# parking.net
KiCad netlist of a schematic drawn in EAGLE
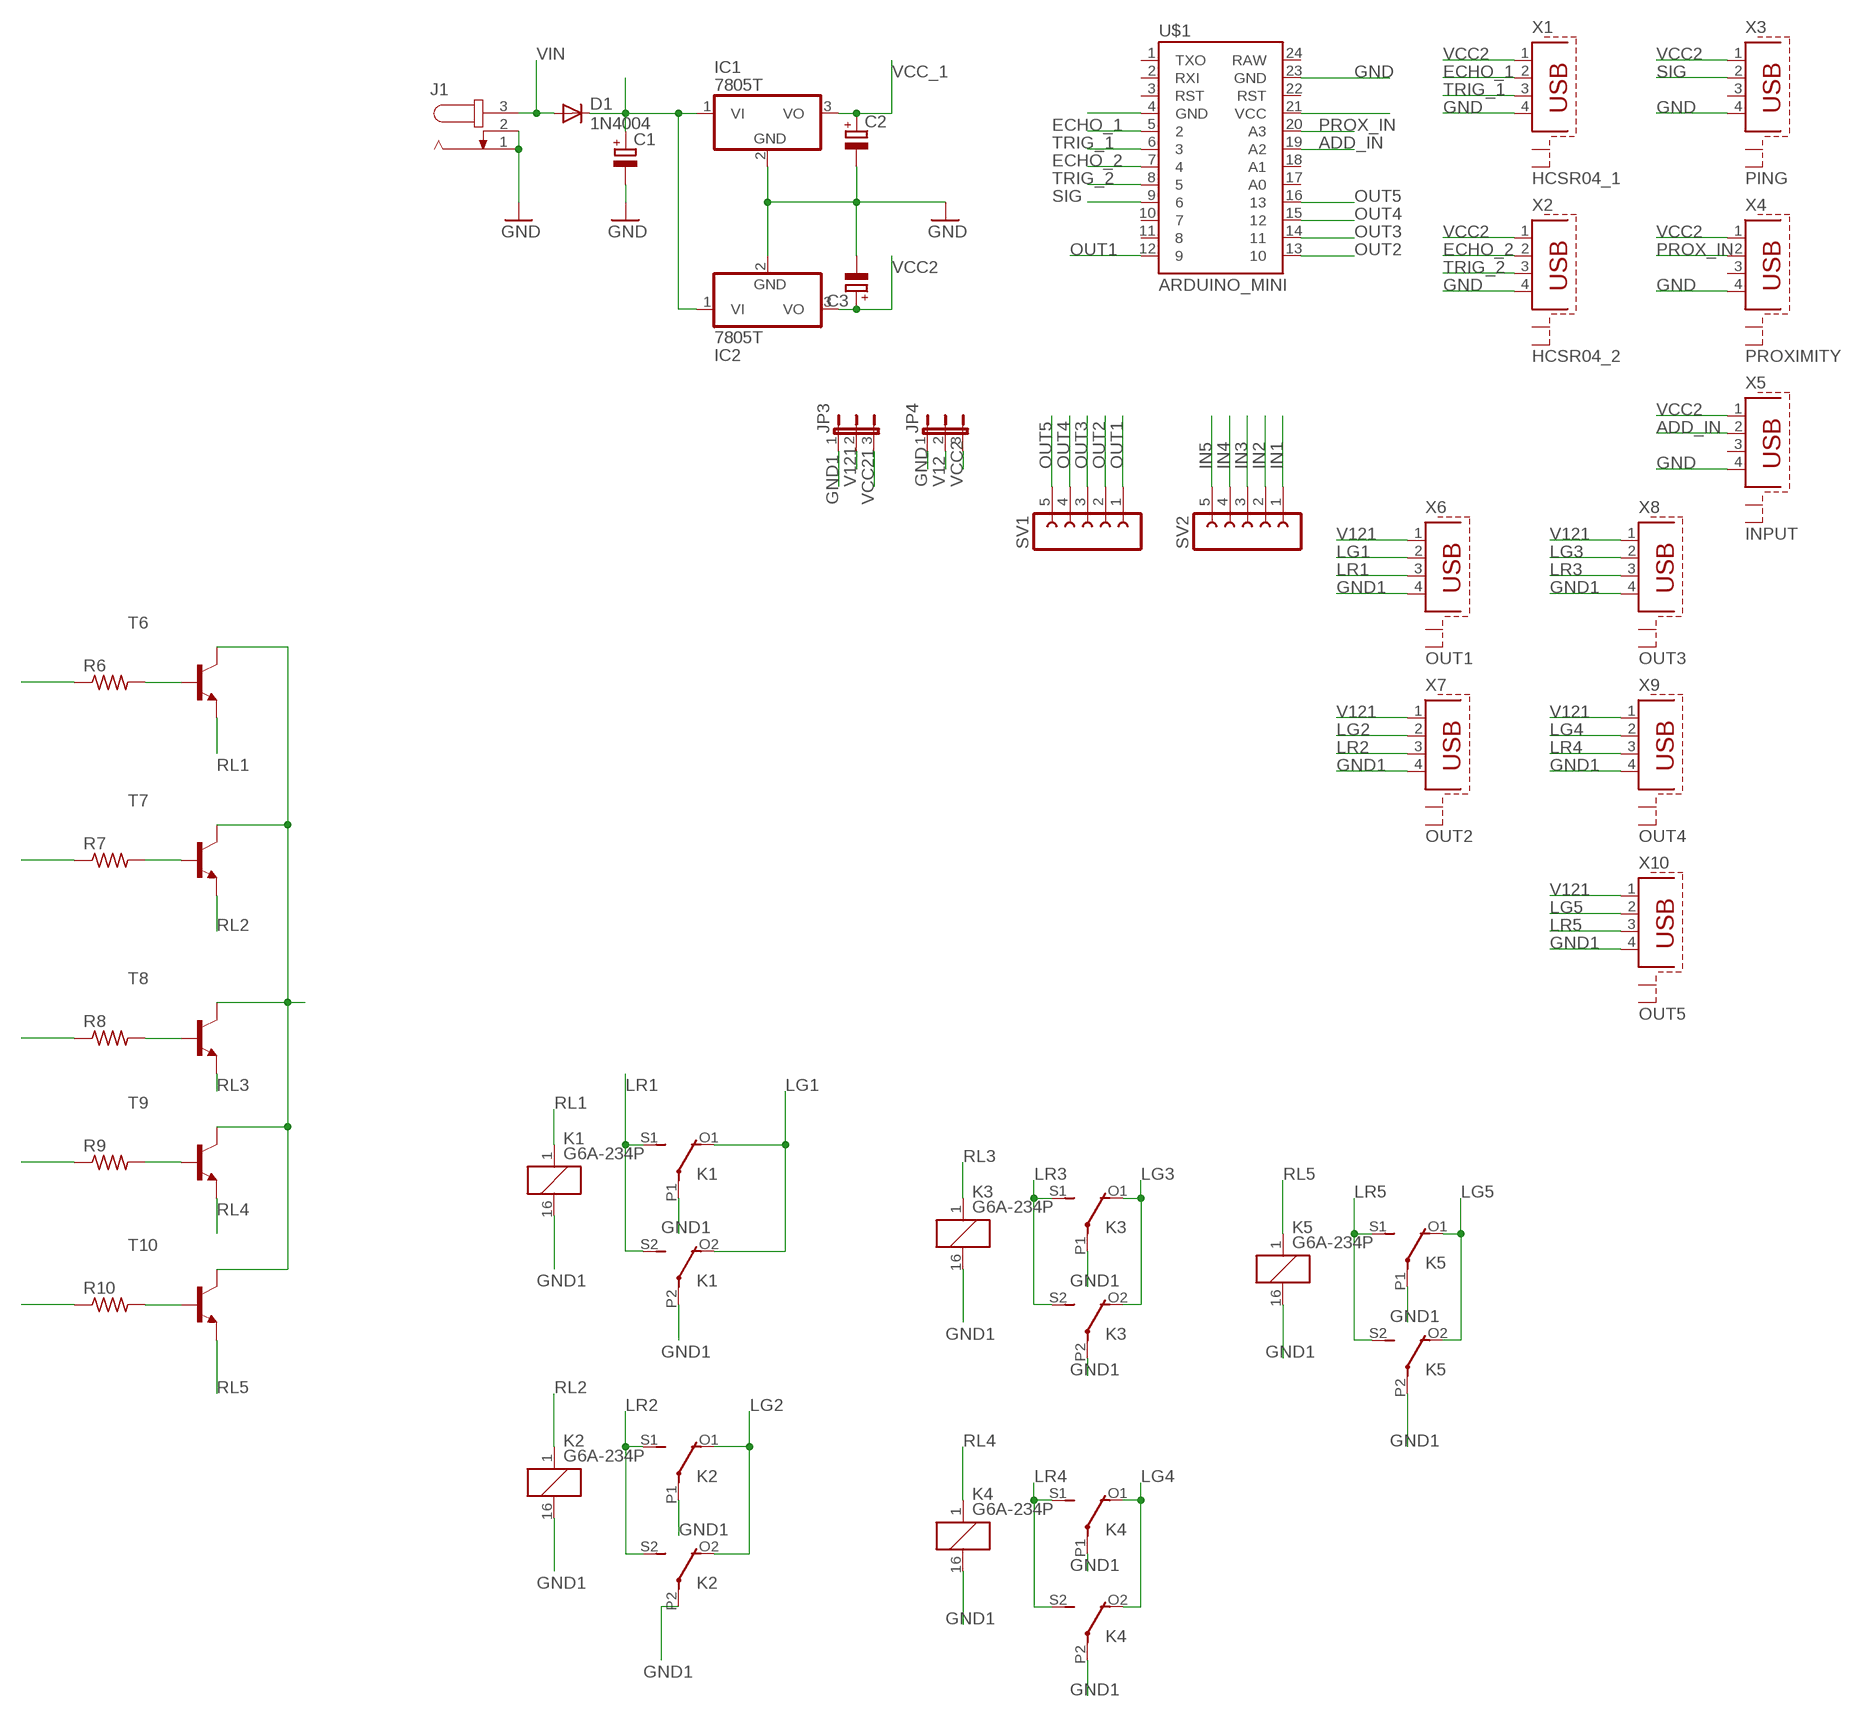
[diagram p0: schematic, sheet 1]

(export (version "E")
  (design (tool "Eeschema 10.0.6"))
  (components
    (comp (ref "C1")
      (value "CPOL-EUE5-10.5")
      (footprint "eagle-import:E5-10,5")
      (libsource (lib "eagle-import") (part "CPOL-EUE5-10.5"))
    )
    (comp (ref "C2")
      (value "CPOL-EUE2.5-5")
      (footprint "eagle-import:E2,5-5")
      (libsource (lib "eagle-import") (part "CPOL-EUE2.5-5"))
    )
    (comp (ref "C3")
      (value "CPOL-EUE2.5-5")
      (footprint "eagle-import:E2,5-5")
      (libsource (lib "eagle-import") (part "CPOL-EUE2.5-5"))
    )
    (comp (ref "D1")
      (value "1N4004")
      (footprint "eagle-import:DO41-10")
      (libsource (lib "eagle-import") (part "1N4004"))
    )
    (comp (ref "IC1")
      (value "7805T")
      (footprint "eagle-import:TO220H")
      (libsource (lib "eagle-import") (part "78T05"))
    )
    (comp (ref "IC2")
      (value "7805T")
      (footprint "eagle-import:TO220H")
      (libsource (lib "eagle-import") (part "78T05"))
    )
    (comp (ref "J1")
      (value "JACK-PLUG1")
      (footprint "eagle-import:SPC4078")
      (libsource (lib "eagle-import") (part "JACK-PLUG1"))
    )
    (comp (ref "JP3")
      (value "JP2E")
      (footprint "eagle-import:JP2")
      (libsource (lib "eagle-import") (part "JP2E"))
    )
    (comp (ref "JP4")
      (value "JP2E")
      (footprint "eagle-import:JP2")
      (libsource (lib "eagle-import") (part "JP2E"))
    )
    (comp (ref "K1")
      (value "G6A-234P")
      (footprint "eagle-import:G6A-234P")
      (libsource (lib "eagle-import") (part "G6A-234P"))
    )
    (comp (ref "K2")
      (value "G6A-234P")
      (footprint "eagle-import:G6A-234P")
      (libsource (lib "eagle-import") (part "G6A-234P"))
    )
    (comp (ref "K3")
      (value "G6A-234P")
      (footprint "eagle-import:G6A-234P")
      (libsource (lib "eagle-import") (part "G6A-234P"))
    )
    (comp (ref "K4")
      (value "G6A-234P")
      (footprint "eagle-import:G6A-234P")
      (libsource (lib "eagle-import") (part "G6A-234P"))
    )
    (comp (ref "K5")
      (value "G6A-234P")
      (footprint "eagle-import:G6A-234P")
      (libsource (lib "eagle-import") (part "G6A-234P"))
    )
    (comp (ref "R6")
      (value "R-US_0207/7")
      (footprint "eagle-import:0207_7")
      (libsource (lib "eagle-import") (part "R-US_0207/7"))
    )
    (comp (ref "R7")
      (value "R-US_0207/7")
      (footprint "eagle-import:0207_7")
      (libsource (lib "eagle-import") (part "R-US_0207/7"))
    )
    (comp (ref "R8")
      (value "R-US_0207/7")
      (footprint "eagle-import:0207_7")
      (libsource (lib "eagle-import") (part "R-US_0207/7"))
    )
    (comp (ref "R9")
      (value "R-US_0207/7")
      (footprint "eagle-import:0207_7")
      (libsource (lib "eagle-import") (part "R-US_0207/7"))
    )
    (comp (ref "R10")
      (value "R-US_0207/7")
      (footprint "eagle-import:0207_7")
      (libsource (lib "eagle-import") (part "R-US_0207/7"))
    )
    (comp (ref "SV1")
      (value "FE05-1")
      (footprint "eagle-import:FE05-1")
      (libsource (lib "eagle-import") (part "FE05-1"))
    )
    (comp (ref "SV2")
      (value "FE05-1")
      (footprint "eagle-import:FE05-1")
      (libsource (lib "eagle-import") (part "FE05-1"))
    )
    (comp (ref "T6")
      (value "BC317-NPN-TO92-EBC")
      (footprint "eagle-import:TO92-EBC")
      (libsource (lib "eagle-import") (part "-NPN-TO92-EBCBC317"))
    )
    (comp (ref "T7")
      (value "BC317-NPN-TO92-EBC")
      (footprint "eagle-import:TO92-EBC")
      (libsource (lib "eagle-import") (part "-NPN-TO92-EBCBC317"))
    )
    (comp (ref "T8")
      (value "BC317-NPN-TO92-EBC")
      (footprint "eagle-import:TO92-EBC")
      (libsource (lib "eagle-import") (part "-NPN-TO92-EBCBC317"))
    )
    (comp (ref "T9")
      (value "BC317-NPN-TO92-EBC")
      (footprint "eagle-import:TO92-EBC")
      (libsource (lib "eagle-import") (part "-NPN-TO92-EBCBC317"))
    )
    (comp (ref "T10")
      (value "BC317-NPN-TO92-EBC")
      (footprint "eagle-import:TO92-EBC")
      (libsource (lib "eagle-import") (part "-NPN-TO92-EBCBC317"))
    )
    (comp (ref "U$1")
      (value "ARDUINO_MINI")
      (footprint "eagle-import:ARDUINO_MINI")
      (libsource (lib "eagle-import") (part "ARDUINO_MINI"))
    )
    (comp (ref "X1")
      (value "HCSR04_1")
      (footprint "eagle-import:PN87520-S")
      (libsource (lib "eagle-import") (part "PN87520-S"))
    )
    (comp (ref "X2")
      (value "HCSR04_2")
      (footprint "eagle-import:PN87520-S")
      (libsource (lib "eagle-import") (part "PN87520-S"))
    )
    (comp (ref "X3")
      (value "PING")
      (footprint "eagle-import:PN87520-S")
      (libsource (lib "eagle-import") (part "PN87520-S"))
    )
    (comp (ref "X4")
      (value "PROXIMITY")
      (footprint "eagle-import:PN87520-S")
      (libsource (lib "eagle-import") (part "PN87520-S"))
    )
    (comp (ref "X5")
      (value "INPUT")
      (footprint "eagle-import:PN87520-S")
      (libsource (lib "eagle-import") (part "PN87520-S"))
    )
    (comp (ref "X6")
      (value "OUT1")
      (footprint "eagle-import:PN87520-S")
      (libsource (lib "eagle-import") (part "PN87520-S"))
    )
    (comp (ref "X7")
      (value "OUT2")
      (footprint "eagle-import:PN87520-S")
      (libsource (lib "eagle-import") (part "PN87520-S"))
    )
    (comp (ref "X8")
      (value "OUT3")
      (footprint "eagle-import:PN87520-S")
      (libsource (lib "eagle-import") (part "PN87520-S"))
    )
    (comp (ref "X9")
      (value "OUT4")
      (footprint "eagle-import:PN87520-S")
      (libsource (lib "eagle-import") (part "PN87520-S"))
    )
    (comp (ref "X10")
      (value "OUT5")
      (footprint "eagle-import:PN87520-S")
      (libsource (lib "eagle-import") (part "PN87520-S"))
    )
  )
  (nets
    (net (code "1") (name "/ADD_IN") (class "Default")
      (node (ref "U$1") (pin "19") (pinfunction "A2_19") (pintype "bidirectional"))
      (node (ref "X5") (pin "2") (pinfunction "2_2") (pintype "passive"))
    )
    (net (code "2") (name "/ECHO_1") (class "Default")
      (node (ref "U$1") (pin "5") (pinfunction "2_5") (pintype "bidirectional"))
      (node (ref "X1") (pin "2") (pinfunction "2_2") (pintype "passive"))
    )
    (net (code "3") (name "/ECHO_2") (class "Default")
      (node (ref "U$1") (pin "7") (pinfunction "4_7") (pintype "bidirectional"))
      (node (ref "X2") (pin "2") (pinfunction "2_2") (pintype "passive"))
    )
    (net (code "4") (name "/GND1") (class "Default")
      (node (ref "JP3") (pin "1") (pinfunction "1_1") (pintype "passive"))
      (node (ref "K1") (pin "16") (pinfunction "2_16") (pintype "passive"))
      (node (ref "K1") (pin "P1") (pinfunction "P_P1") (pintype "passive"))
      (node (ref "K1") (pin "P2") (pinfunction "P_P2") (pintype "passive"))
      (node (ref "K2") (pin "16") (pinfunction "2_16") (pintype "passive"))
      (node (ref "K2") (pin "P1") (pinfunction "P_P1") (pintype "passive"))
      (node (ref "K2") (pin "P2") (pinfunction "P_P2") (pintype "passive"))
      (node (ref "K3") (pin "16") (pinfunction "2_16") (pintype "passive"))
      (node (ref "K3") (pin "P1") (pinfunction "P_P1") (pintype "passive"))
      (node (ref "K3") (pin "P2") (pinfunction "P_P2") (pintype "passive"))
      (node (ref "K4") (pin "16") (pinfunction "2_16") (pintype "passive"))
      (node (ref "K4") (pin "P1") (pinfunction "P_P1") (pintype "passive"))
      (node (ref "K4") (pin "P2") (pinfunction "P_P2") (pintype "passive"))
      (node (ref "K5") (pin "16") (pinfunction "2_16") (pintype "passive"))
      (node (ref "K5") (pin "P1") (pinfunction "P_P1") (pintype "passive"))
      (node (ref "K5") (pin "P2") (pinfunction "P_P2") (pintype "passive"))
      (node (ref "X10") (pin "4") (pinfunction "4_4") (pintype "passive"))
      (node (ref "X6") (pin "4") (pinfunction "4_4") (pintype "passive"))
      (node (ref "X7") (pin "4") (pinfunction "4_4") (pintype "passive"))
      (node (ref "X8") (pin "4") (pinfunction "4_4") (pintype "passive"))
      (node (ref "X9") (pin "4") (pinfunction "4_4") (pintype "passive"))
    )
    (net (code "5") (name "/IN1") (class "Default")
      (node (ref "R6") (pin "1") (pinfunction "1_1") (pintype "passive"))
      (node (ref "SV2") (pin "1") (pinfunction "1_1") (pintype "passive"))
    )
    (net (code "6") (name "/IN2") (class "Default")
      (node (ref "R7") (pin "1") (pinfunction "1_1") (pintype "passive"))
      (node (ref "SV2") (pin "2") (pinfunction "2_2") (pintype "passive"))
    )
    (net (code "7") (name "/IN3") (class "Default")
      (node (ref "R8") (pin "1") (pinfunction "1_1") (pintype "passive"))
      (node (ref "SV2") (pin "3") (pinfunction "3_3") (pintype "passive"))
    )
    (net (code "8") (name "/IN4") (class "Default")
      (node (ref "R9") (pin "1") (pinfunction "1_1") (pintype "passive"))
      (node (ref "SV2") (pin "4") (pinfunction "4_4") (pintype "passive"))
    )
    (net (code "9") (name "/IN5") (class "Default")
      (node (ref "R10") (pin "1") (pinfunction "1_1") (pintype "passive"))
      (node (ref "SV2") (pin "5") (pinfunction "5_5") (pintype "passive"))
    )
    (net (code "10") (name "/LG1") (class "Default")
      (node (ref "K1") (pin "O1") (pinfunction "O_O1") (pintype "passive"))
      (node (ref "K1") (pin "O2") (pinfunction "O_O2") (pintype "passive"))
      (node (ref "X6") (pin "2") (pinfunction "2_2") (pintype "passive"))
    )
    (net (code "11") (name "/LG2") (class "Default")
      (node (ref "K2") (pin "O1") (pinfunction "O_O1") (pintype "passive"))
      (node (ref "K2") (pin "O2") (pinfunction "O_O2") (pintype "passive"))
      (node (ref "X7") (pin "2") (pinfunction "2_2") (pintype "passive"))
    )
    (net (code "12") (name "/LG3") (class "Default")
      (node (ref "K3") (pin "O1") (pinfunction "O_O1") (pintype "passive"))
      (node (ref "K3") (pin "O2") (pinfunction "O_O2") (pintype "passive"))
      (node (ref "X8") (pin "2") (pinfunction "2_2") (pintype "passive"))
    )
    (net (code "13") (name "/LG4") (class "Default")
      (node (ref "K4") (pin "O1") (pinfunction "O_O1") (pintype "passive"))
      (node (ref "K4") (pin "O2") (pinfunction "O_O2") (pintype "passive"))
      (node (ref "X9") (pin "2") (pinfunction "2_2") (pintype "passive"))
    )
    (net (code "14") (name "/LG5") (class "Default")
      (node (ref "K5") (pin "O1") (pinfunction "O_O1") (pintype "passive"))
      (node (ref "K5") (pin "O2") (pinfunction "O_O2") (pintype "passive"))
      (node (ref "X10") (pin "2") (pinfunction "2_2") (pintype "passive"))
    )
    (net (code "15") (name "/LR1") (class "Default")
      (node (ref "K1") (pin "S1") (pinfunction "S_S1") (pintype "passive"))
      (node (ref "K1") (pin "S2") (pinfunction "S_S2") (pintype "passive"))
      (node (ref "X6") (pin "3") (pinfunction "3_3") (pintype "passive"))
    )
    (net (code "16") (name "/LR2") (class "Default")
      (node (ref "K2") (pin "S1") (pinfunction "S_S1") (pintype "passive"))
      (node (ref "K2") (pin "S2") (pinfunction "S_S2") (pintype "passive"))
      (node (ref "X7") (pin "3") (pinfunction "3_3") (pintype "passive"))
    )
    (net (code "17") (name "/LR3") (class "Default")
      (node (ref "K3") (pin "S1") (pinfunction "S_S1") (pintype "passive"))
      (node (ref "K3") (pin "S2") (pinfunction "S_S2") (pintype "passive"))
      (node (ref "X8") (pin "3") (pinfunction "3_3") (pintype "passive"))
    )
    (net (code "18") (name "/LR4") (class "Default")
      (node (ref "K4") (pin "S1") (pinfunction "S_S1") (pintype "passive"))
      (node (ref "K4") (pin "S2") (pinfunction "S_S2") (pintype "passive"))
      (node (ref "X9") (pin "3") (pinfunction "3_3") (pintype "passive"))
    )
    (net (code "19") (name "/LR5") (class "Default")
      (node (ref "K5") (pin "S1") (pinfunction "S_S1") (pintype "passive"))
      (node (ref "K5") (pin "S2") (pinfunction "S_S2") (pintype "passive"))
      (node (ref "X10") (pin "3") (pinfunction "3_3") (pintype "passive"))
    )
    (net (code "20") (name "/OUT1") (class "Default")
      (node (ref "SV1") (pin "1") (pinfunction "1_1") (pintype "passive"))
      (node (ref "U$1") (pin "12") (pinfunction "9_12") (pintype "bidirectional"))
    )
    (net (code "21") (name "/OUT2") (class "Default")
      (node (ref "SV1") (pin "2") (pinfunction "2_2") (pintype "passive"))
      (node (ref "U$1") (pin "13") (pinfunction "10_13") (pintype "bidirectional"))
    )
    (net (code "22") (name "/OUT3") (class "Default")
      (node (ref "SV1") (pin "3") (pinfunction "3_3") (pintype "passive"))
      (node (ref "U$1") (pin "14") (pinfunction "11_14") (pintype "bidirectional"))
    )
    (net (code "23") (name "/OUT4") (class "Default")
      (node (ref "SV1") (pin "4") (pinfunction "4_4") (pintype "passive"))
      (node (ref "U$1") (pin "15") (pinfunction "12_15") (pintype "bidirectional"))
    )
    (net (code "24") (name "/OUT5") (class "Default")
      (node (ref "SV1") (pin "5") (pinfunction "5_5") (pintype "passive"))
      (node (ref "U$1") (pin "16") (pinfunction "13_16") (pintype "bidirectional"))
    )
    (net (code "25") (name "/PROX_IN") (class "Default")
      (node (ref "U$1") (pin "20") (pinfunction "A3_20") (pintype "bidirectional"))
      (node (ref "X4") (pin "2") (pinfunction "2_2") (pintype "passive"))
    )
    (net (code "26") (name "/RL1") (class "Default")
      (node (ref "K1") (pin "1") (pinfunction "1_1") (pintype "passive"))
      (node (ref "T6") (pin "E") (pinfunction "E_E") (pintype "passive"))
    )
    (net (code "27") (name "/RL2") (class "Default")
      (node (ref "K2") (pin "1") (pinfunction "1_1") (pintype "passive"))
      (node (ref "T7") (pin "E") (pinfunction "E_E") (pintype "passive"))
    )
    (net (code "28") (name "/RL3") (class "Default")
      (node (ref "K3") (pin "1") (pinfunction "1_1") (pintype "passive"))
      (node (ref "T8") (pin "E") (pinfunction "E_E") (pintype "passive"))
    )
    (net (code "29") (name "/RL4") (class "Default")
      (node (ref "K4") (pin "1") (pinfunction "1_1") (pintype "passive"))
      (node (ref "T9") (pin "E") (pinfunction "E_E") (pintype "passive"))
    )
    (net (code "30") (name "/RL5") (class "Default")
      (node (ref "K5") (pin "1") (pinfunction "1_1") (pintype "passive"))
      (node (ref "T10") (pin "E") (pinfunction "E_E") (pintype "passive"))
    )
    (net (code "31") (name "/SIG") (class "Default")
      (node (ref "U$1") (pin "9") (pinfunction "6_9") (pintype "bidirectional"))
      (node (ref "X3") (pin "2") (pinfunction "2_2") (pintype "passive"))
    )
    (net (code "32") (name "/TRIG_1") (class "Default")
      (node (ref "U$1") (pin "6") (pinfunction "3_6") (pintype "bidirectional"))
      (node (ref "X1") (pin "3") (pinfunction "3_3") (pintype "passive"))
    )
    (net (code "33") (name "/TRIG_2") (class "Default")
      (node (ref "U$1") (pin "8") (pinfunction "5_8") (pintype "bidirectional"))
      (node (ref "X2") (pin "3") (pinfunction "3_3") (pintype "passive"))
    )
    (net (code "34") (name "/V12") (class "Default")
      (node (ref "C1") (pin "+") (pinfunction "+_+") (pintype "passive"))
      (node (ref "D1") (pin "C") (pinfunction "C_C") (pintype "passive"))
      (node (ref "IC1") (pin "1") (pinfunction "VI_1") (pintype "input"))
      (node (ref "IC2") (pin "1") (pinfunction "VI_1") (pintype "input"))
      (node (ref "JP4") (pin "2") (pinfunction "2_2") (pintype "passive"))
    )
    (net (code "35") (name "/V121") (class "Default")
      (node (ref "JP3") (pin "2") (pinfunction "2_2") (pintype "passive"))
      (node (ref "X10") (pin "1") (pinfunction "1_1") (pintype "passive"))
      (node (ref "X6") (pin "1") (pinfunction "1_1") (pintype "passive"))
      (node (ref "X7") (pin "1") (pinfunction "1_1") (pintype "passive"))
      (node (ref "X8") (pin "1") (pinfunction "1_1") (pintype "passive"))
      (node (ref "X9") (pin "1") (pinfunction "1_1") (pintype "passive"))
    )
    (net (code "36") (name "/VCC2") (class "Default")
      (node (ref "C3") (pin "+") (pinfunction "+_+") (pintype "passive"))
      (node (ref "IC2") (pin "3") (pinfunction "VO_3") (pintype "passive"))
      (node (ref "JP4") (pin "3") (pinfunction "3_3") (pintype "passive"))
      (node (ref "X1") (pin "1") (pinfunction "1_1") (pintype "passive"))
      (node (ref "X2") (pin "1") (pinfunction "1_1") (pintype "passive"))
      (node (ref "X3") (pin "1") (pinfunction "1_1") (pintype "passive"))
      (node (ref "X4") (pin "1") (pinfunction "1_1") (pintype "passive"))
      (node (ref "X5") (pin "1") (pinfunction "1_1") (pintype "passive"))
    )
    (net (code "37") (name "/VCC21") (class "Default")
      (node (ref "JP3") (pin "3") (pinfunction "3_3") (pintype "passive"))
      (node (ref "T10") (pin "C") (pinfunction "C_C") (pintype "passive"))
      (node (ref "T6") (pin "C") (pinfunction "C_C") (pintype "passive"))
      (node (ref "T7") (pin "C") (pinfunction "C_C") (pintype "passive"))
      (node (ref "T8") (pin "C") (pinfunction "C_C") (pintype "passive"))
      (node (ref "T9") (pin "C") (pinfunction "C_C") (pintype "passive"))
    )
    (net (code "38") (name "/VCC_1") (class "Default")
      (node (ref "C2") (pin "+") (pinfunction "+_+") (pintype "passive"))
      (node (ref "IC1") (pin "3") (pinfunction "VO_3") (pintype "passive"))
      (node (ref "U$1") (pin "21") (pinfunction "VCC_21") (pintype "bidirectional"))
    )
    (net (code "39") (name "/VIN") (class "Default")
      (node (ref "D1") (pin "A") (pinfunction "A_A") (pintype "passive"))
      (node (ref "J1") (pin "3") (pinfunction "3_3") (pintype "passive"))
    )
    (net (code "40") (name "GND") (class "Default")
      (node (ref "C1") (pin "-") (pinfunction "-_-") (pintype "passive"))
      (node (ref "C2") (pin "-") (pinfunction "-_-") (pintype "passive"))
      (node (ref "C3") (pin "-") (pinfunction "-_-") (pintype "passive"))
      (node (ref "IC1") (pin "2") (pinfunction "GND_2") (pintype "passive"))
      (node (ref "IC2") (pin "2") (pinfunction "GND_2") (pintype "passive"))
      (node (ref "J1") (pin "1") (pinfunction "1_1") (pintype "passive"))
      (node (ref "J1") (pin "2") (pinfunction "2_2") (pintype "passive"))
      (node (ref "JP4") (pin "1") (pinfunction "1_1") (pintype "passive"))
      (node (ref "U$1") (pin "23") (pinfunction "GND_23") (pintype "bidirectional"))
      (node (ref "U$1") (pin "4") (pinfunction "GND_4") (pintype "bidirectional"))
      (node (ref "X1") (pin "4") (pinfunction "4_4") (pintype "passive"))
      (node (ref "X2") (pin "4") (pinfunction "4_4") (pintype "passive"))
      (node (ref "X3") (pin "4") (pinfunction "4_4") (pintype "passive"))
      (node (ref "X4") (pin "4") (pinfunction "4_4") (pintype "passive"))
      (node (ref "X5") (pin "4") (pinfunction "4_4") (pintype "passive"))
    )
    (net (code "41") (name "Net-(R6-Pad2)") (class "Default")
      (node (ref "R6") (pin "2") (pinfunction "2_2") (pintype "passive"))
      (node (ref "T6") (pin "B") (pinfunction "B_B") (pintype "passive"))
    )
    (net (code "42") (name "Net-(R7-Pad2)") (class "Default")
      (node (ref "R7") (pin "2") (pinfunction "2_2") (pintype "passive"))
      (node (ref "T7") (pin "B") (pinfunction "B_B") (pintype "passive"))
    )
    (net (code "43") (name "Net-(R8-Pad2)") (class "Default")
      (node (ref "R8") (pin "2") (pinfunction "2_2") (pintype "passive"))
      (node (ref "T8") (pin "B") (pinfunction "B_B") (pintype "passive"))
    )
    (net (code "44") (name "Net-(R9-Pad2)") (class "Default")
      (node (ref "R9") (pin "2") (pinfunction "2_2") (pintype "passive"))
      (node (ref "T9") (pin "B") (pinfunction "B_B") (pintype "passive"))
    )
    (net (code "45") (name "Net-(R10-Pad2)") (class "Default")
      (node (ref "R10") (pin "2") (pinfunction "2_2") (pintype "passive"))
      (node (ref "T10") (pin "B") (pinfunction "B_B") (pintype "passive"))
    )
    (net (code "46") (name "unconnected-(U$1-7-Pad10)") (class "Default")
      (node (ref "U$1") (pin "10") (pinfunction "7_10") (pintype "bidirectional"))
    )
    (net (code "47") (name "unconnected-(U$1-8-Pad11)") (class "Default")
      (node (ref "U$1") (pin "11") (pinfunction "8_11") (pintype "bidirectional"))
    )
    (net (code "48") (name "unconnected-(U$1-A0-Pad17)") (class "Default")
      (node (ref "U$1") (pin "17") (pinfunction "A0_17") (pintype "bidirectional"))
    )
    (net (code "49") (name "unconnected-(U$1-A1-Pad18)") (class "Default")
      (node (ref "U$1") (pin "18") (pinfunction "A1_18") (pintype "bidirectional"))
    )
    (net (code "50") (name "unconnected-(U$1-RAW-Pad24)") (class "Default")
      (node (ref "U$1") (pin "24") (pinfunction "RAW_24") (pintype "bidirectional"))
    )
    (net (code "51") (name "unconnected-(U$1-RST-Pad3)") (class "Default")
      (node (ref "U$1") (pin "3") (pinfunction "RST_3") (pintype "bidirectional"))
    )
    (net (code "52") (name "unconnected-(U$1-RST-Pad22)") (class "Default")
      (node (ref "U$1") (pin "22") (pinfunction "RST_22") (pintype "bidirectional"))
    )
    (net (code "53") (name "unconnected-(U$1-RXI-Pad2)") (class "Default")
      (node (ref "U$1") (pin "2") (pinfunction "RXI_2") (pintype "bidirectional"))
    )
    (net (code "54") (name "unconnected-(U$1-TXO-Pad1)") (class "Default")
      (node (ref "U$1") (pin "1") (pinfunction "TXO_1") (pintype "bidirectional"))
    )
    (net (code "55") (name "unconnected-(X1-PadS1)") (class "Default")
      (node (ref "X1") (pin "S1") (pinfunction "S1_S1") (pintype "passive"))
    )
    (net (code "56") (name "unconnected-(X1-PadS2)") (class "Default")
      (node (ref "X1") (pin "S2") (pinfunction "S2_S2") (pintype "passive"))
    )
    (net (code "57") (name "unconnected-(X2-PadS1)") (class "Default")
      (node (ref "X2") (pin "S1") (pinfunction "S1_S1") (pintype "passive"))
    )
    (net (code "58") (name "unconnected-(X2-PadS2)") (class "Default")
      (node (ref "X2") (pin "S2") (pinfunction "S2_S2") (pintype "passive"))
    )
    (net (code "59") (name "unconnected-(X3-Pad3)") (class "Default")
      (node (ref "X3") (pin "3") (pinfunction "3_3") (pintype "passive"))
    )
    (net (code "60") (name "unconnected-(X3-PadS1)") (class "Default")
      (node (ref "X3") (pin "S1") (pinfunction "S1_S1") (pintype "passive"))
    )
    (net (code "61") (name "unconnected-(X3-PadS2)") (class "Default")
      (node (ref "X3") (pin "S2") (pinfunction "S2_S2") (pintype "passive"))
    )
    (net (code "62") (name "unconnected-(X4-Pad3)") (class "Default")
      (node (ref "X4") (pin "3") (pinfunction "3_3") (pintype "passive"))
    )
    (net (code "63") (name "unconnected-(X4-PadS1)") (class "Default")
      (node (ref "X4") (pin "S1") (pinfunction "S1_S1") (pintype "passive"))
    )
    (net (code "64") (name "unconnected-(X4-PadS2)") (class "Default")
      (node (ref "X4") (pin "S2") (pinfunction "S2_S2") (pintype "passive"))
    )
    (net (code "65") (name "unconnected-(X5-Pad3)") (class "Default")
      (node (ref "X5") (pin "3") (pinfunction "3_3") (pintype "passive"))
    )
    (net (code "66") (name "unconnected-(X5-PadS1)") (class "Default")
      (node (ref "X5") (pin "S1") (pinfunction "S1_S1") (pintype "passive"))
    )
    (net (code "67") (name "unconnected-(X5-PadS2)") (class "Default")
      (node (ref "X5") (pin "S2") (pinfunction "S2_S2") (pintype "passive"))
    )
    (net (code "68") (name "unconnected-(X6-PadS1)") (class "Default")
      (node (ref "X6") (pin "S1") (pinfunction "S1_S1") (pintype "passive"))
    )
    (net (code "69") (name "unconnected-(X6-PadS2)") (class "Default")
      (node (ref "X6") (pin "S2") (pinfunction "S2_S2") (pintype "passive"))
    )
    (net (code "70") (name "unconnected-(X7-PadS1)") (class "Default")
      (node (ref "X7") (pin "S1") (pinfunction "S1_S1") (pintype "passive"))
    )
    (net (code "71") (name "unconnected-(X7-PadS2)") (class "Default")
      (node (ref "X7") (pin "S2") (pinfunction "S2_S2") (pintype "passive"))
    )
    (net (code "72") (name "unconnected-(X8-PadS1)") (class "Default")
      (node (ref "X8") (pin "S1") (pinfunction "S1_S1") (pintype "passive"))
    )
    (net (code "73") (name "unconnected-(X8-PadS2)") (class "Default")
      (node (ref "X8") (pin "S2") (pinfunction "S2_S2") (pintype "passive"))
    )
    (net (code "74") (name "unconnected-(X9-PadS1)") (class "Default")
      (node (ref "X9") (pin "S1") (pinfunction "S1_S1") (pintype "passive"))
    )
    (net (code "75") (name "unconnected-(X9-PadS2)") (class "Default")
      (node (ref "X9") (pin "S2") (pinfunction "S2_S2") (pintype "passive"))
    )
    (net (code "76") (name "unconnected-(X10-PadS1)") (class "Default")
      (node (ref "X10") (pin "S1") (pinfunction "S1_S1") (pintype "passive"))
    )
    (net (code "77") (name "unconnected-(X10-PadS2)") (class "Default")
      (node (ref "X10") (pin "S2") (pinfunction "S2_S2") (pintype "passive"))
    )
  )
)
